# avr_keyboard_toy.net
KiCad netlist of a schematic drawn in EAGLE
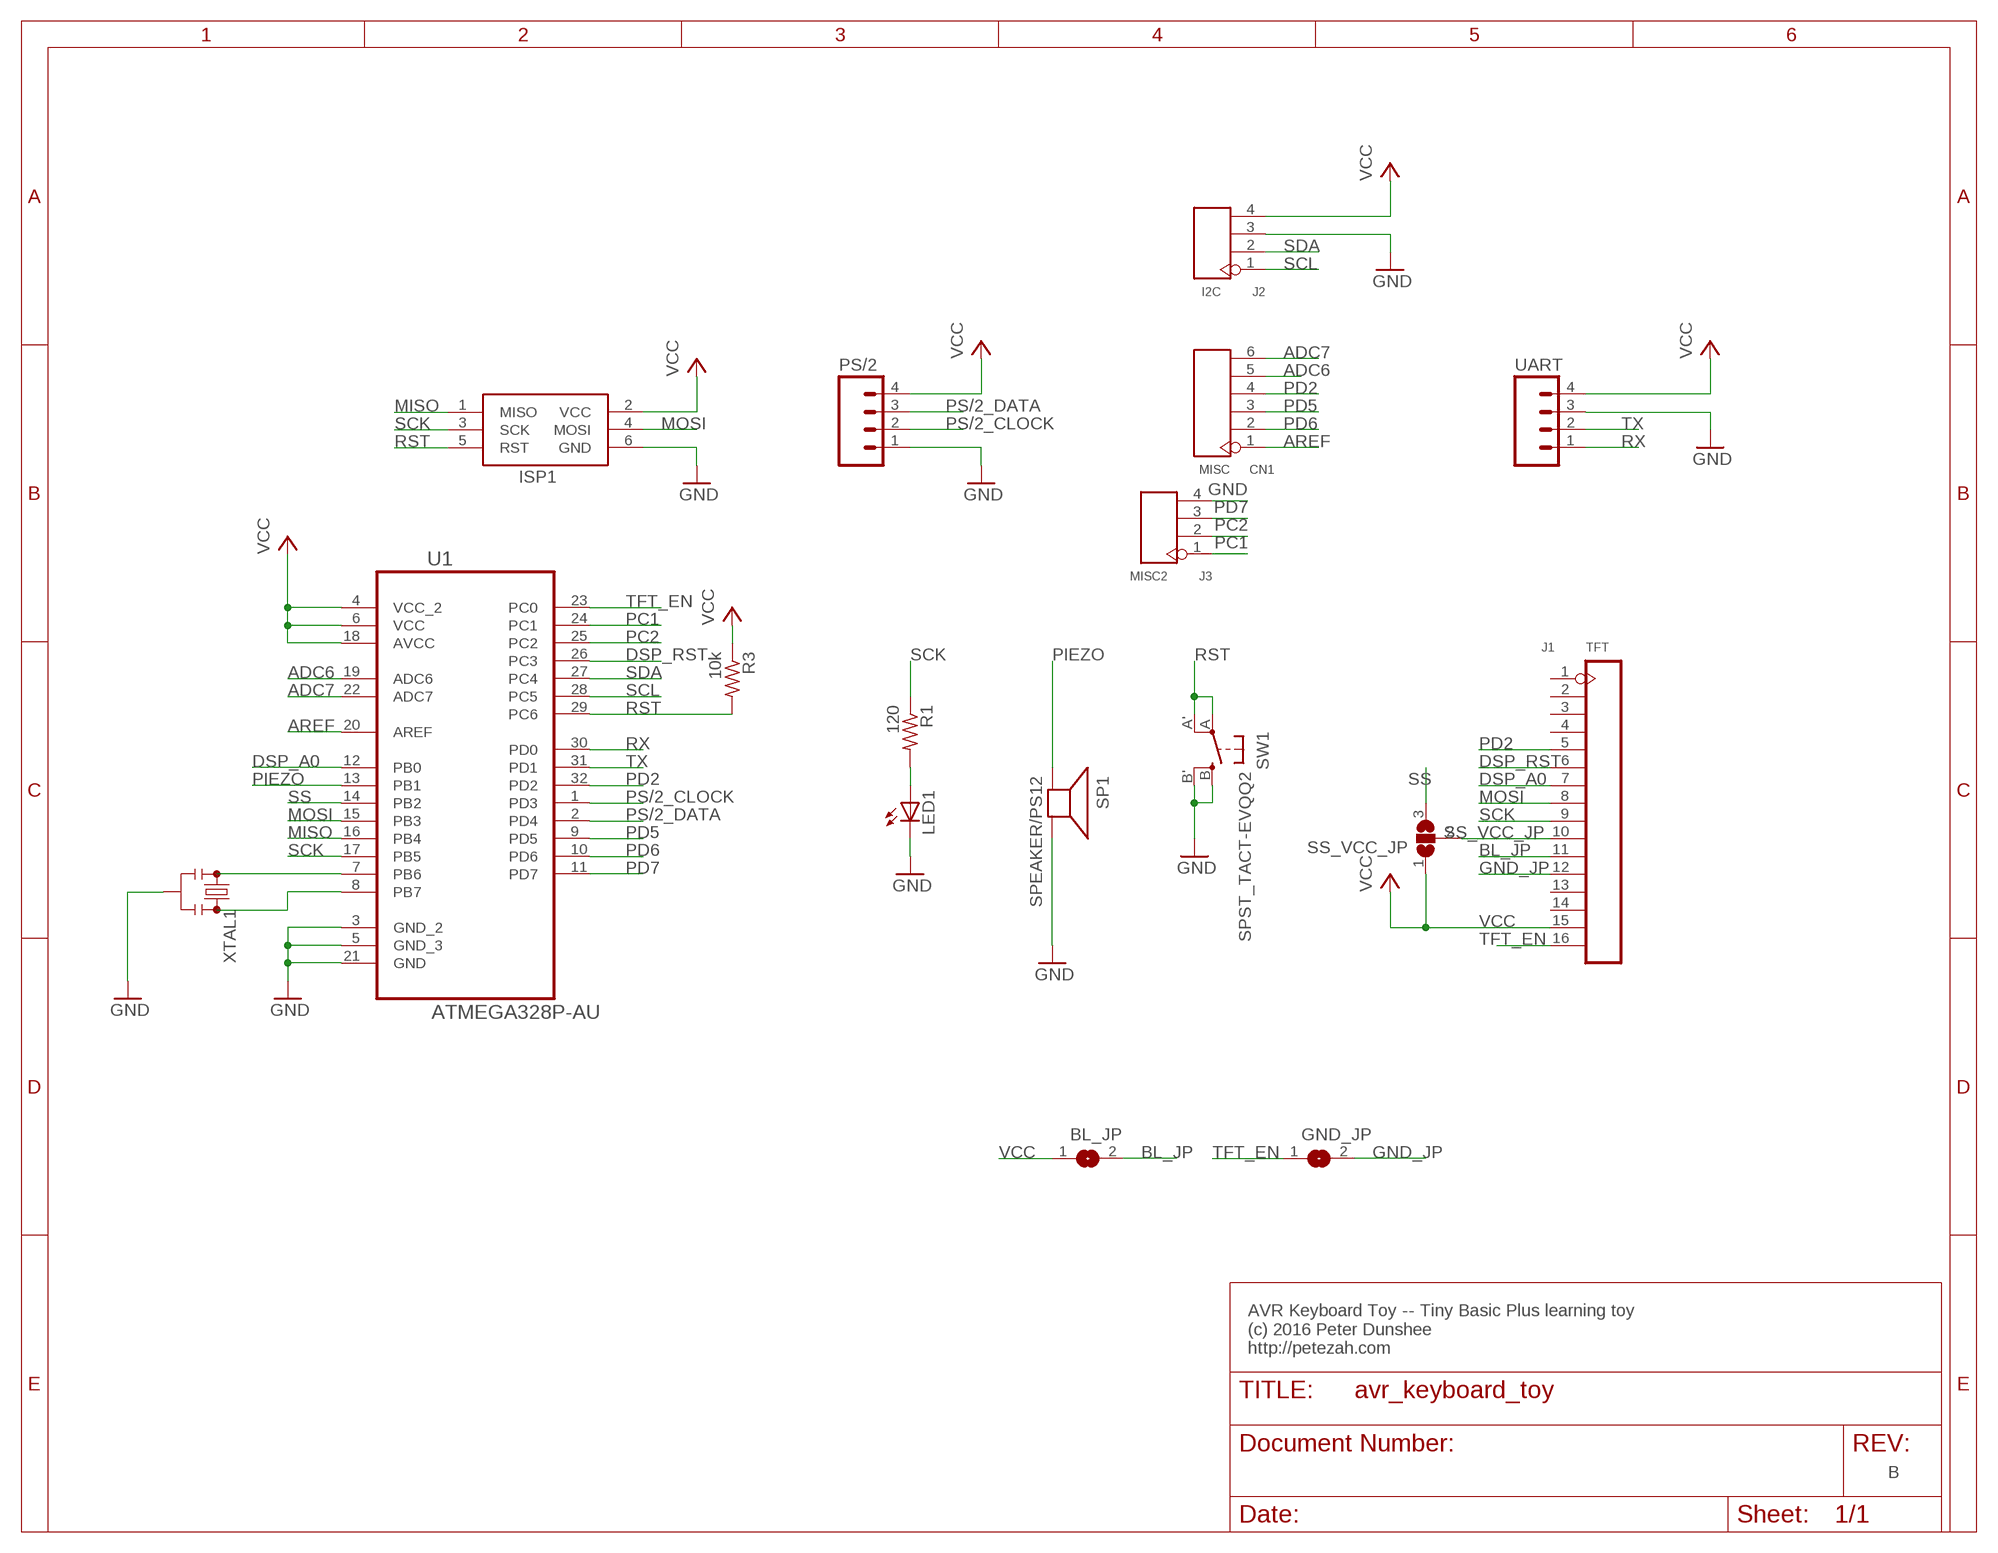
[diagram p0: schematic, sheet 1]

(export (version "E")
  (design (tool "Eeschema 10.0.6"))
  (components
    (comp (ref "BL_JP")
      (value "SJ")
      (footprint "eagle-import:SJ")
      (libsource (lib "eagle-import") (part "SJ"))
    )
    (comp (ref "CN1")
      (value "MISC")
      (footprint "eagle-import:H6-2.54")
      (fields (field (name "MPN") "F185-1106A1BSYC1"))
      (libsource (lib "eagle-import") (part "DIP-BLACK-FEMALE-HEADER-VERT(6P-2.54)"))
    )
    (comp (ref "GND_JP")
      (value "SJ")
      (footprint "eagle-import:SJ")
      (libsource (lib "eagle-import") (part "SJ"))
    )
    (comp (ref "ISP1")
      (value "AVRISP-6")
      (footprint "eagle-import:AVRISP")
      (libsource (lib "eagle-import") (part "AVRISP-6"))
    )
    (comp (ref "J1")
      (value "TFT")
      (footprint "eagle-import:H16-2.54")
      (fields (field (name "MPN") "F185-1116A0BSYA1"))
      (libsource (lib "eagle-import") (part "DIP-BLACK-FEMALE-HEADER-VERT(16P-2.54)"))
    )
    (comp (ref "J2")
      (value "I2C")
      (footprint "eagle-import:H4-2.54")
      (fields (field (name "MPN") "F185-1104A1BSYA1"))
      (libsource (lib "eagle-import") (part "DIP-BLACK-FEMALE-HEADER-VERT(4P-2.54)"))
    )
    (comp (ref "J3")
      (value "MISC2")
      (footprint "eagle-import:H4-2.54")
      (fields (field (name "MPN") "F185-1104A1BSYA1"))
      (libsource (lib "eagle-import") (part "DIP-BLACK-FEMALE-HEADER-VERT(4P-2.54)"))
    )
    (comp (ref "LED1")
      (value "LEDCHIPLED_1206")
      (footprint "eagle-import:CHIPLED_1206")
      (libsource (lib "eagle-import") (part "LEDCHIPLED_1206"))
    )
    (comp (ref "PS/2")
      (value "M04PTH")
      (footprint "eagle-import:1X04")
      (libsource (lib "eagle-import") (part "M04PTH"))
    )
    (comp (ref "R1")
      (value "120")
      (footprint "eagle-import:R1206")
      (libsource (lib "eagle-import") (part "R-US_R1206"))
    )
    (comp (ref "R3")
      (value "10k")
      (footprint "eagle-import:R1206")
      (libsource (lib "eagle-import") (part "R-US_R1206"))
    )
    (comp (ref "SP1")
      (value "SPEAKER/PS12")
      (footprint "eagle-import:PS12")
      (libsource (lib "eagle-import") (part "SPEAKER/PS12"))
    )
    (comp (ref "SS_VCC_JP")
      (value "SJ2W")
      (footprint "eagle-import:SJ_2")
      (libsource (lib "eagle-import") (part "SJ2W"))
    )
    (comp (ref "SW1")
      (value "SPST_TACT-EVQQ2")
      (footprint "eagle-import:EVQ-Q2")
      (libsource (lib "eagle-import") (part "SPST_TACT-EVQQ2"))
    )
    (comp (ref "U1")
      (value "ATMEGA328P-AU")
      (footprint "eagle-import:QFP80P900X900X120-32N")
      (libsource (lib "eagle-import") (part "ATMEGA328P-AU"))
    )
    (comp (ref "UART")
      (value "M04PTH")
      (footprint "eagle-import:1X04")
      (libsource (lib "eagle-import") (part "M04PTH"))
    )
    (comp (ref "XTAL1")
      (value "RESONATORPTH")
      (footprint "eagle-import:RESONATOR-PTH")
      (libsource (lib "eagle-import") (part "RESONATORPTH"))
    )
  )
  (nets
    (net (code "1") (name "/ADC6") (class "Default")
      (node (ref "CN1") (pin "5") (pinfunction "5_5") (pintype "bidirectional"))
      (node (ref "U1") (pin "19") (pinfunction "ADC6_19") (pintype "input"))
    )
    (net (code "2") (name "/ADC7") (class "Default")
      (node (ref "CN1") (pin "6") (pinfunction "6_6") (pintype "bidirectional"))
      (node (ref "U1") (pin "22") (pinfunction "ADC7_22") (pintype "input"))
    )
    (net (code "3") (name "/AREF") (class "Default")
      (node (ref "CN1") (pin "1") (pinfunction "1_1") (pintype "bidirectional"))
      (node (ref "U1") (pin "20") (pinfunction "AREF_20") (pintype "input"))
    )
    (net (code "4") (name "/BL_JP") (class "Default")
      (node (ref "BL_JP") (pin "2") (pinfunction "2_2") (pintype "passive"))
      (node (ref "J1") (pin "11") (pinfunction "11_11") (pintype "passive"))
    )
    (net (code "5") (name "/DSP_A0") (class "Default")
      (node (ref "J1") (pin "7") (pinfunction "7_7") (pintype "passive"))
      (node (ref "U1") (pin "12") (pinfunction "PB0_12") (pintype "bidirectional"))
    )
    (net (code "6") (name "/DSP_RST") (class "Default")
      (node (ref "J1") (pin "6") (pinfunction "6_6") (pintype "passive"))
      (node (ref "U1") (pin "26") (pinfunction "PC3_26") (pintype "bidirectional"))
    )
    (net (code "7") (name "/GND_JP") (class "Default")
      (node (ref "GND_JP") (pin "2") (pinfunction "2_2") (pintype "passive"))
      (node (ref "J1") (pin "12") (pinfunction "12_12") (pintype "passive"))
    )
    (net (code "8") (name "/MISO") (class "Default")
      (node (ref "ISP1") (pin "1") (pinfunction "MISO_1") (pintype "input"))
      (node (ref "U1") (pin "16") (pinfunction "PB4_16") (pintype "bidirectional"))
    )
    (net (code "9") (name "/MOSI") (class "Default")
      (node (ref "ISP1") (pin "4") (pinfunction "MOSI_4") (pintype "output"))
      (node (ref "J1") (pin "8") (pinfunction "8_8") (pintype "passive"))
      (node (ref "U1") (pin "15") (pinfunction "PB3_15") (pintype "bidirectional"))
    )
    (net (code "10") (name "/PC1") (class "Default")
      (node (ref "J3") (pin "1") (pinfunction "P$1_1") (pintype "bidirectional"))
      (node (ref "U1") (pin "24") (pinfunction "PC1_24") (pintype "bidirectional"))
    )
    (net (code "11") (name "/PC2") (class "Default")
      (node (ref "J3") (pin "2") (pinfunction "P$2_2") (pintype "bidirectional"))
      (node (ref "U1") (pin "25") (pinfunction "PC2_25") (pintype "bidirectional"))
    )
    (net (code "12") (name "/PD2") (class "Default")
      (node (ref "CN1") (pin "4") (pinfunction "4_4") (pintype "bidirectional"))
      (node (ref "J1") (pin "5") (pinfunction "5_5") (pintype "passive"))
      (node (ref "U1") (pin "32") (pinfunction "PD2_32") (pintype "bidirectional"))
    )
    (net (code "13") (name "/PD5") (class "Default")
      (node (ref "CN1") (pin "3") (pinfunction "3_3") (pintype "bidirectional"))
      (node (ref "U1") (pin "9") (pinfunction "PD5_9") (pintype "bidirectional"))
    )
    (net (code "14") (name "/PD6") (class "Default")
      (node (ref "CN1") (pin "2") (pinfunction "2_2") (pintype "bidirectional"))
      (node (ref "U1") (pin "10") (pinfunction "PD6_10") (pintype "bidirectional"))
    )
    (net (code "15") (name "/PD7") (class "Default")
      (node (ref "J3") (pin "3") (pinfunction "P$3_3") (pintype "bidirectional"))
      (node (ref "U1") (pin "11") (pinfunction "PD7_11") (pintype "bidirectional"))
    )
    (net (code "16") (name "/PIEZO") (class "Default")
      (node (ref "SP1") (pin "P$1") (pinfunction "+_P$1") (pintype "passive"))
      (node (ref "U1") (pin "13") (pinfunction "PB1_13") (pintype "bidirectional"))
    )
    (net (code "17") (name "/PS{slash}2_CLOCK") (class "Default")
      (node (ref "PS/2") (pin "2") (pinfunction "2_2") (pintype "passive"))
      (node (ref "U1") (pin "1") (pinfunction "PD3_1") (pintype "bidirectional"))
    )
    (net (code "18") (name "/PS{slash}2_DATA") (class "Default")
      (node (ref "PS/2") (pin "3") (pinfunction "3_3") (pintype "passive"))
      (node (ref "U1") (pin "2") (pinfunction "PD4_2") (pintype "bidirectional"))
    )
    (net (code "19") (name "/RST") (class "Default")
      (node (ref "ISP1") (pin "5") (pinfunction "RST_5") (pintype "output"))
      (node (ref "R3") (pin "2") (pinfunction "2_2") (pintype "passive"))
      (node (ref "SW1") (pin "A") (pinfunction "P_A") (pintype "passive"))
      (node (ref "SW1") (pin "A'") (pinfunction "P1_A'") (pintype "passive"))
      (node (ref "U1") (pin "29") (pinfunction "PC6_29") (pintype "bidirectional"))
    )
    (net (code "20") (name "/RX") (class "Default")
      (node (ref "U1") (pin "30") (pinfunction "PD0_30") (pintype "bidirectional"))
      (node (ref "UART") (pin "1") (pinfunction "1_1") (pintype "passive"))
    )
    (net (code "21") (name "/SCK") (class "Default")
      (node (ref "ISP1") (pin "3") (pinfunction "SCK_3") (pintype "output"))
      (node (ref "J1") (pin "9") (pinfunction "9_9") (pintype "passive"))
      (node (ref "R1") (pin "1") (pinfunction "1_1") (pintype "passive"))
      (node (ref "U1") (pin "17") (pinfunction "PB5_17") (pintype "bidirectional"))
    )
    (net (code "22") (name "/SCL") (class "Default")
      (node (ref "J2") (pin "1") (pinfunction "P$1_1") (pintype "bidirectional"))
      (node (ref "U1") (pin "28") (pinfunction "PC5_28") (pintype "bidirectional"))
    )
    (net (code "23") (name "/SDA") (class "Default")
      (node (ref "J2") (pin "2") (pinfunction "P$2_2") (pintype "bidirectional"))
      (node (ref "U1") (pin "27") (pinfunction "PC4_27") (pintype "bidirectional"))
    )
    (net (code "24") (name "/SS") (class "Default")
      (node (ref "SS_VCC_JP") (pin "3") (pinfunction "3_3") (pintype "passive"))
      (node (ref "U1") (pin "14") (pinfunction "PB2_14") (pintype "bidirectional"))
    )
    (net (code "25") (name "/SS_VCC_JP") (class "Default")
      (node (ref "J1") (pin "10") (pinfunction "10_10") (pintype "passive"))
      (node (ref "SS_VCC_JP") (pin "2") (pinfunction "2_2") (pintype "passive"))
    )
    (net (code "26") (name "/TFT_EN") (class "Default")
      (node (ref "GND_JP") (pin "1") (pinfunction "1_1") (pintype "passive"))
      (node (ref "J1") (pin "16") (pinfunction "16_16") (pintype "passive"))
      (node (ref "U1") (pin "23") (pinfunction "PC0_23") (pintype "bidirectional"))
    )
    (net (code "27") (name "/TX") (class "Default")
      (node (ref "U1") (pin "31") (pinfunction "PD1_31") (pintype "bidirectional"))
      (node (ref "UART") (pin "2") (pinfunction "2_2") (pintype "passive"))
    )
    (net (code "28") (name "GND") (class "Default")
      (node (ref "ISP1") (pin "6") (pinfunction "GND_6") (pintype "power_in"))
      (node (ref "J2") (pin "3") (pinfunction "P$3_3") (pintype "bidirectional"))
      (node (ref "J3") (pin "4") (pinfunction "P$4_4") (pintype "bidirectional"))
      (node (ref "LED1") (pin "C") (pinfunction "C_C") (pintype "passive"))
      (node (ref "PS/2") (pin "1") (pinfunction "1_1") (pintype "passive"))
      (node (ref "SP1") (pin "P$2") (pinfunction "-_P$2") (pintype "passive"))
      (node (ref "SW1") (pin "B") (pinfunction "S_B") (pintype "passive"))
      (node (ref "SW1") (pin "B'") (pinfunction "S1_B'") (pintype "passive"))
      (node (ref "U1") (pin "21") (pinfunction "GND_21") (pintype "passive"))
      (node (ref "U1") (pin "3") (pinfunction "GND_2_3") (pintype "passive"))
      (node (ref "U1") (pin "5") (pinfunction "GND_3_5") (pintype "passive"))
      (node (ref "UART") (pin "3") (pinfunction "3_3") (pintype "passive"))
      (node (ref "XTAL1") (pin "2") (pinfunction "2_2") (pintype "passive"))
    )
    (net (code "29") (name "Net-(LED1-PadA)") (class "Default")
      (node (ref "LED1") (pin "A") (pinfunction "A_A") (pintype "passive"))
      (node (ref "R1") (pin "2") (pinfunction "2_2") (pintype "passive"))
    )
    (net (code "30") (name "Net-(U1-PB6)") (class "Default")
      (node (ref "U1") (pin "7") (pinfunction "PB6_7") (pintype "bidirectional"))
      (node (ref "XTAL1") (pin "1") (pinfunction "1_1") (pintype "passive"))
    )
    (net (code "31") (name "Net-(U1-PB7)") (class "Default")
      (node (ref "U1") (pin "8") (pinfunction "PB7_8") (pintype "bidirectional"))
      (node (ref "XTAL1") (pin "3") (pinfunction "3_3") (pintype "passive"))
    )
    (net (code "32") (name "VCC") (class "Default")
      (node (ref "BL_JP") (pin "1") (pinfunction "1_1") (pintype "passive"))
      (node (ref "ISP1") (pin "2") (pinfunction "VCC_2") (pintype "power_in"))
      (node (ref "J1") (pin "15") (pinfunction "15_15") (pintype "passive"))
      (node (ref "J2") (pin "4") (pinfunction "P$4_4") (pintype "bidirectional"))
      (node (ref "PS/2") (pin "4") (pinfunction "4_4") (pintype "passive"))
      (node (ref "R3") (pin "1") (pinfunction "1_1") (pintype "passive"))
      (node (ref "SS_VCC_JP") (pin "1") (pinfunction "1_1") (pintype "passive"))
      (node (ref "U1") (pin "18") (pinfunction "AVCC_18") (pintype "power_in"))
      (node (ref "U1") (pin "4") (pinfunction "VCC_2_4") (pintype "power_in"))
      (node (ref "U1") (pin "6") (pinfunction "VCC_6") (pintype "power_in"))
      (node (ref "UART") (pin "4") (pinfunction "4_4") (pintype "passive"))
    )
    (net (code "33") (name "unconnected-(J1-Pad1)") (class "Default")
      (node (ref "J1") (pin "1") (pinfunction "1_1") (pintype "passive"))
    )
    (net (code "34") (name "unconnected-(J1-Pad2)") (class "Default")
      (node (ref "J1") (pin "2") (pinfunction "2_2") (pintype "passive"))
    )
    (net (code "35") (name "unconnected-(J1-Pad3)") (class "Default")
      (node (ref "J1") (pin "3") (pinfunction "3_3") (pintype "passive"))
    )
    (net (code "36") (name "unconnected-(J1-Pad4)") (class "Default")
      (node (ref "J1") (pin "4") (pinfunction "4_4") (pintype "passive"))
    )
    (net (code "37") (name "unconnected-(J1-Pad13)") (class "Default")
      (node (ref "J1") (pin "13") (pinfunction "13_13") (pintype "passive"))
    )
    (net (code "38") (name "unconnected-(J1-Pad14)") (class "Default")
      (node (ref "J1") (pin "14") (pinfunction "14_14") (pintype "passive"))
    )
  )
)
